# 4_Resistor_Sensor.net
KiCad netlist of a schematic drawn in Altium Designer
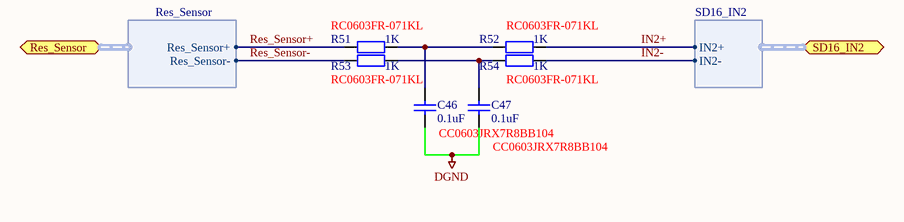
[diagram p0: 4_Resistor_Sensor.SchDoc]

(export (version "E")
  (design (tool "Eeschema 10.0.6"))
  (components
    (comp (ref "C46")
      (value "0.1uF")
      (footprint "CC0603")
      (description "Capacitor")
      (fields (field (name "TYPE NO.") "CC0603JRX7R8BB104"))
      (libsource (lib "Miscellaneous Devices") (part "Cap"))
    )
    (comp (ref "C47")
      (value "0.1uF")
      (footprint "CC0603")
      (description "Capacitor")
      (fields (field (name "TYPE NO.") "CC0603JRX7R8BB104"))
      (libsource (lib "Miscellaneous Devices") (part "Cap"))
    )
    (comp (ref "R51")
      (value "1K")
      (footprint "CC0603")
      (description "Resistor")
      (fields (field (name "TYPE NO.") "RC0603FR-071KL"))
      (libsource (lib "Miscellaneous Devices") (part "Res2"))
    )
    (comp (ref "R52")
      (value "1K")
      (footprint "CC0603")
      (description "Resistor")
      (fields (field (name "TYPE NO.") "RC0603FR-071KL"))
      (libsource (lib "Miscellaneous Devices") (part "Res2"))
    )
    (comp (ref "R53")
      (value "1K")
      (footprint "CC0603")
      (description "Resistor")
      (fields (field (name "TYPE NO.") "RC0603FR-071KL"))
      (libsource (lib "Miscellaneous Devices") (part "Res2"))
    )
    (comp (ref "R54")
      (value "1K")
      (footprint "CC0603")
      (description "Resistor")
      (fields (field (name "TYPE NO.") "RC0603FR-071KL"))
      (libsource (lib "Miscellaneous Devices") (part "Res2"))
    )
  )
  (nets
    (net (code "3") (name "/IN2+") (class "Default")
      (node (ref "R52") (pin "1") (pinfunction "1_1") (pintype "passive"))
    )
    (net (code "4") (name "/IN2-") (class "Default")
      (node (ref "R54") (pin "1") (pinfunction "1_1") (pintype "passive"))
    )
    (net (code "5") (name "/Res_Sensor+") (class "Default")
      (node (ref "R51") (pin "2") (pinfunction "2_2") (pintype "passive"))
    )
    (net (code "6") (name "/Res_Sensor-") (class "Default")
      (node (ref "R53") (pin "2") (pinfunction "2_2") (pintype "passive"))
    )
    (net (code "9") (name "DGND") (class "Default")
      (node (ref "C46") (pin "2") (pinfunction "2_2") (pintype "passive"))
      (node (ref "C47") (pin "2") (pinfunction "2_2") (pintype "passive"))
    )
    (net (code "10") (name "Net-(C46-Pad1)") (class "Default")
      (node (ref "C46") (pin "1") (pinfunction "1_1") (pintype "passive"))
      (node (ref "R51") (pin "1") (pinfunction "1_1") (pintype "passive"))
      (node (ref "R52") (pin "2") (pinfunction "2_2") (pintype "passive"))
    )
    (net (code "11") (name "Net-(C47-Pad1)") (class "Default")
      (node (ref "C47") (pin "1") (pinfunction "1_1") (pintype "passive"))
      (node (ref "R53") (pin "1") (pinfunction "1_1") (pintype "passive"))
      (node (ref "R54") (pin "2") (pinfunction "2_2") (pintype "passive"))
    )
  )
)
